# Board.net
KiCad netlist of a schematic drawn in EAGLE
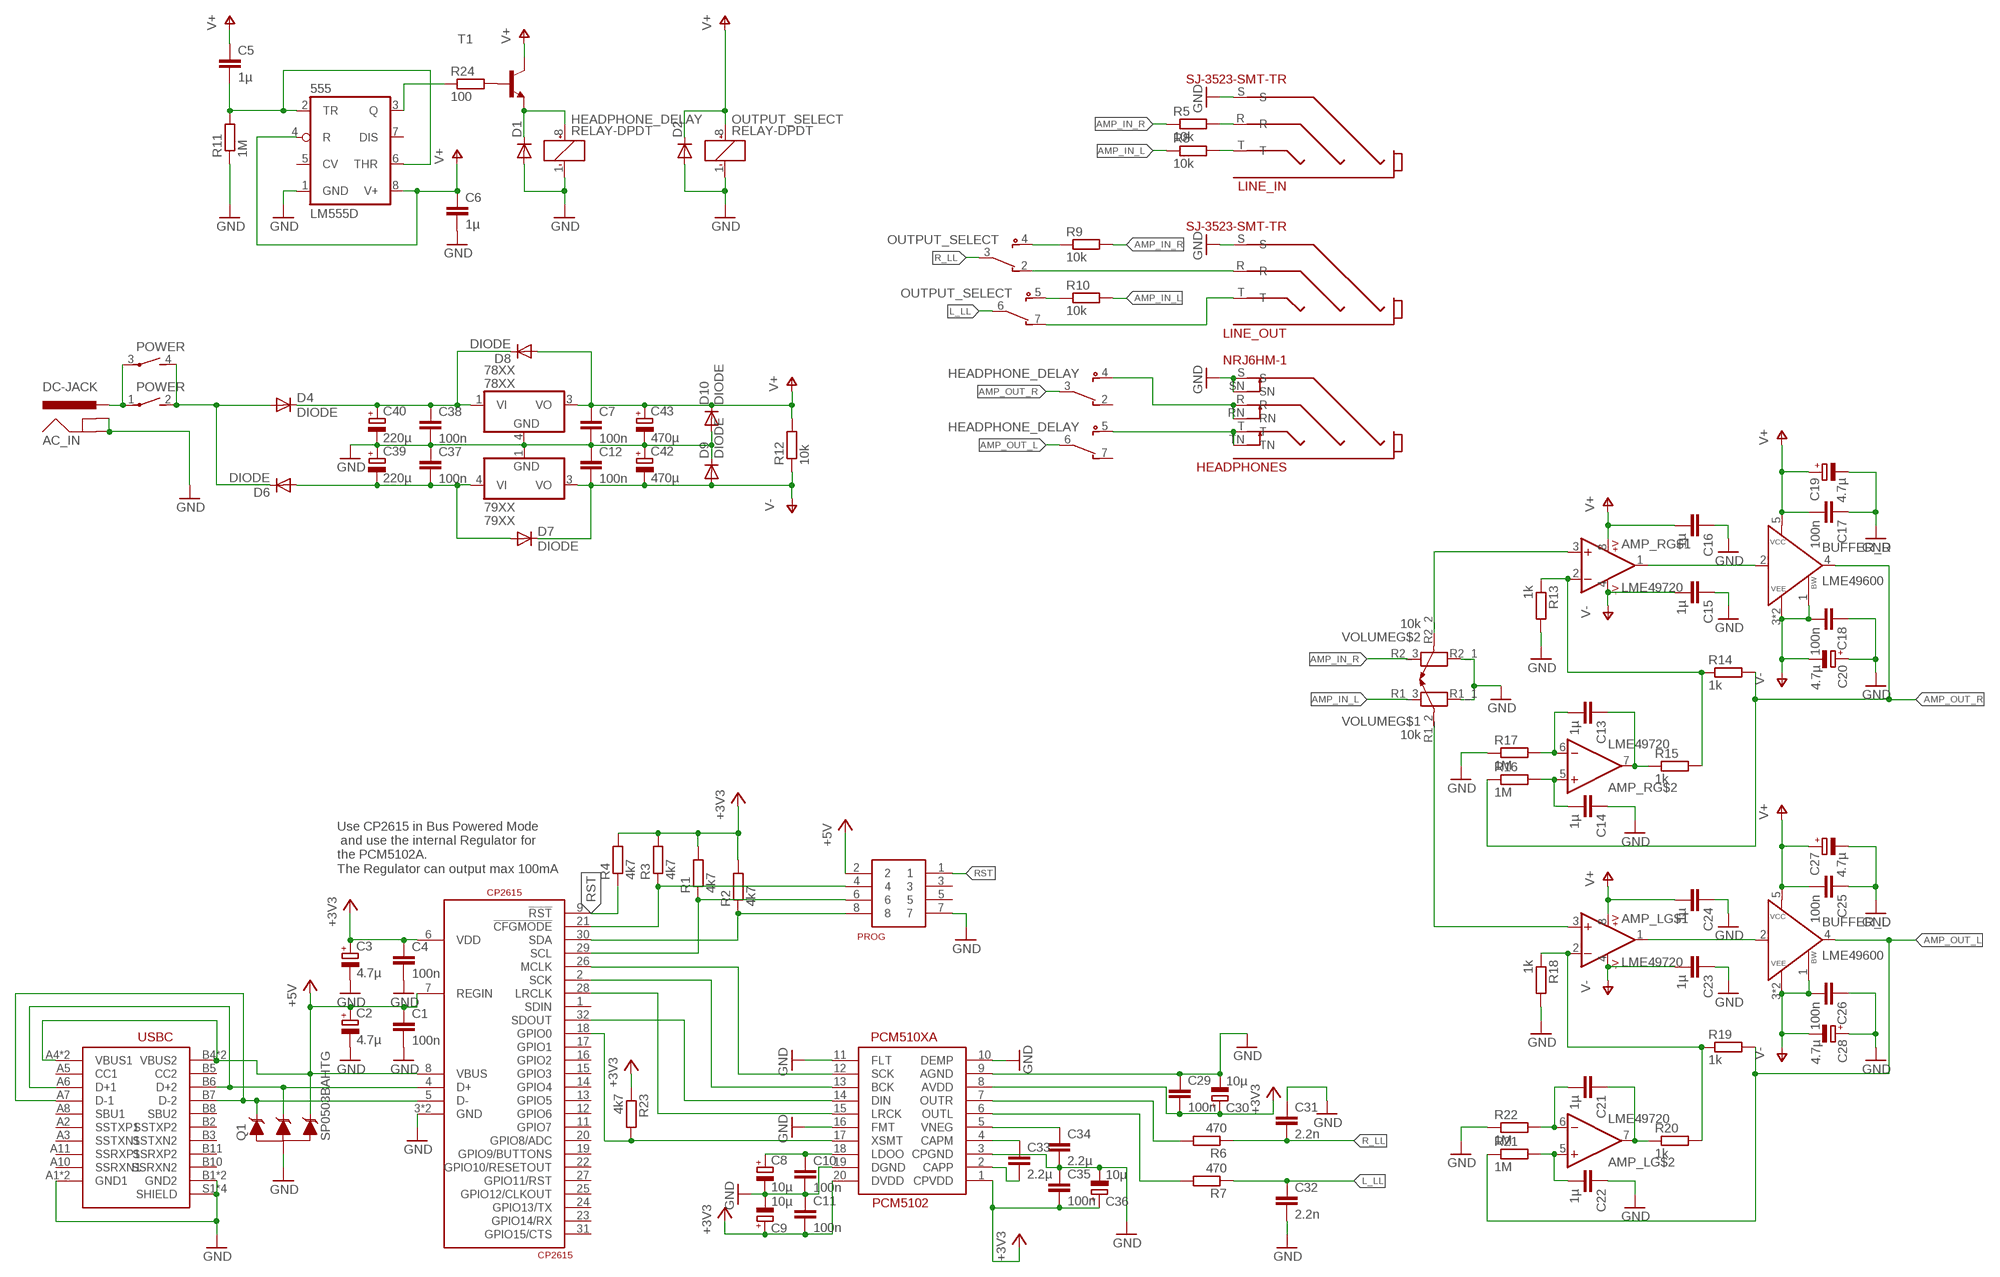
[diagram p0: schematic, sheet 1]

(export (version "E")
  (design (tool "Eeschema 10.0.6"))
  (components
    (comp (ref "78XX")
      (value "78XX")
      (footprint "eagle-import:D2PAK")
      (libsource (lib "eagle-import") (part "78XX"))
    )
    (comp (ref "79XX")
      (value "79XX")
      (footprint "eagle-import:D2PAK")
      (libsource (lib "eagle-import") (part "79XX"))
    )
    (comp (ref "555")
      (value "LM555D")
      (footprint "eagle-import:SO08")
      (libsource (lib "eagle-import") (part "555DLM"))
    )
    (comp (ref "AC_IN")
      (value "DC-JACK")
      (footprint "eagle-import:POWER_JACK_PTH")
      (libsource (lib "eagle-import") (part "DC-JACK"))
    )
    (comp (ref "AMP_L")
      (value "LME49720")
      (footprint "eagle-import:SOIC127P600X175-8")
      (libsource (lib "eagle-import") (part "LME49720"))
    )
    (comp (ref "AMP_R")
      (value "LME49720")
      (footprint "eagle-import:SOIC127P600X175-8")
      (libsource (lib "eagle-import") (part "LME49720"))
    )
    (comp (ref "BUFFER_L")
      (value "LME49600")
      (footprint "eagle-import:TO170P1238X470-6")
      (libsource (lib "eagle-import") (part "LME49600"))
    )
    (comp (ref "BUFFER_R")
      (value "LME49600")
      (footprint "eagle-import:TO170P1238X470-6")
      (libsource (lib "eagle-import") (part "LME49600"))
    )
    (comp (ref "C1")
      (value "100n")
      (footprint "eagle-import:C0603")
      (libsource (lib "eagle-import") (part "C-EUC0603"))
    )
    (comp (ref "C2")
      (value "4.7µ")
      (footprint "eagle-import:UD-4X5,8_NICHICON")
      (libsource (lib "eagle-import") (part "CPOL-EUUD-4X5,8"))
    )
    (comp (ref "C3")
      (value "4.7µ")
      (footprint "eagle-import:UD-4X5,8_NICHICON")
      (libsource (lib "eagle-import") (part "CPOL-EUUD-4X5,8"))
    )
    (comp (ref "C4")
      (value "100n")
      (footprint "eagle-import:C0603")
      (libsource (lib "eagle-import") (part "C-EUC0603"))
    )
    (comp (ref "C5")
      (value "1µ")
      (footprint "eagle-import:C0603")
      (libsource (lib "eagle-import") (part "C-EUC0603"))
    )
    (comp (ref "C6")
      (value "1µ")
      (footprint "eagle-import:C0603")
      (libsource (lib "eagle-import") (part "C-EUC0603"))
    )
    (comp (ref "C7")
      (value "100n")
      (footprint "eagle-import:C0603")
      (libsource (lib "eagle-import") (part "C-EUC0603"))
    )
    (comp (ref "C8")
      (value "10µ")
      (footprint "eagle-import:UD-4X5,8_NICHICON")
      (libsource (lib "eagle-import") (part "CPOL-EUUD-4X5,8"))
    )
    (comp (ref "C9")
      (value "10µ")
      (footprint "eagle-import:UD-4X5,8_NICHICON")
      (libsource (lib "eagle-import") (part "CPOL-EUUD-4X5,8"))
    )
    (comp (ref "C10")
      (value "100n")
      (footprint "eagle-import:C0603")
      (libsource (lib "eagle-import") (part "C-EUC0603"))
    )
    (comp (ref "C11")
      (value "100n")
      (footprint "eagle-import:C0603")
      (libsource (lib "eagle-import") (part "C-EUC0603"))
    )
    (comp (ref "C12")
      (value "100n")
      (footprint "eagle-import:C0603")
      (libsource (lib "eagle-import") (part "C-EUC0603"))
    )
    (comp (ref "C13")
      (value "1µ")
      (footprint "eagle-import:C0603")
      (libsource (lib "eagle-import") (part "C-EUC0603"))
    )
    (comp (ref "C14")
      (value "1µ")
      (footprint "eagle-import:C0603")
      (libsource (lib "eagle-import") (part "C-EUC0603"))
    )
    (comp (ref "C15")
      (value "1µ")
      (footprint "eagle-import:C0603")
      (libsource (lib "eagle-import") (part "C-EUC0603"))
    )
    (comp (ref "C16")
      (value "1µ")
      (footprint "eagle-import:C0603")
      (libsource (lib "eagle-import") (part "C-EUC0603"))
    )
    (comp (ref "C17")
      (value "100n")
      (footprint "eagle-import:C0603")
      (libsource (lib "eagle-import") (part "C-EUC0603"))
    )
    (comp (ref "C18")
      (value "100n")
      (footprint "eagle-import:C0603")
      (libsource (lib "eagle-import") (part "C-EUC0603"))
    )
    (comp (ref "C19")
      (value "4.7µ")
      (footprint "eagle-import:SMC_A")
      (libsource (lib "eagle-import") (part "CPOL-EUSMCA"))
    )
    (comp (ref "C20")
      (value "4.7µ")
      (footprint "eagle-import:SMC_A")
      (libsource (lib "eagle-import") (part "CPOL-EUSMCA"))
    )
    (comp (ref "C21")
      (value "1µ")
      (footprint "eagle-import:C0603")
      (libsource (lib "eagle-import") (part "C-EUC0603"))
    )
    (comp (ref "C22")
      (value "1µ")
      (footprint "eagle-import:C0603")
      (libsource (lib "eagle-import") (part "C-EUC0603"))
    )
    (comp (ref "C23")
      (value "1µ")
      (footprint "eagle-import:C0603")
      (libsource (lib "eagle-import") (part "C-EUC0603"))
    )
    (comp (ref "C24")
      (value "1µ")
      (footprint "eagle-import:C0603")
      (libsource (lib "eagle-import") (part "C-EUC0603"))
    )
    (comp (ref "C25")
      (value "100n")
      (footprint "eagle-import:C0603")
      (libsource (lib "eagle-import") (part "C-EUC0603"))
    )
    (comp (ref "C26")
      (value "100n")
      (footprint "eagle-import:C0603")
      (libsource (lib "eagle-import") (part "C-EUC0603"))
    )
    (comp (ref "C27")
      (value "4.7µ")
      (footprint "eagle-import:SMC_A")
      (libsource (lib "eagle-import") (part "CPOL-EUSMCA"))
    )
    (comp (ref "C28")
      (value "4.7µ")
      (footprint "eagle-import:SMC_A")
      (libsource (lib "eagle-import") (part "CPOL-EUSMCA"))
    )
    (comp (ref "C29")
      (value "100n")
      (footprint "eagle-import:C0603")
      (libsource (lib "eagle-import") (part "C-EUC0603"))
    )
    (comp (ref "C30")
      (value "10µ")
      (footprint "eagle-import:UD-4X5,8_NICHICON")
      (libsource (lib "eagle-import") (part "CPOL-EUUD-4X5,8"))
    )
    (comp (ref "C31")
      (value "2.2n")
      (footprint "eagle-import:C0603")
      (libsource (lib "eagle-import") (part "C-EUC0603"))
    )
    (comp (ref "C32")
      (value "2.2n")
      (footprint "eagle-import:C0603")
      (libsource (lib "eagle-import") (part "C-EUC0603"))
    )
    (comp (ref "C33")
      (value "2.2µ")
      (footprint "eagle-import:C0603")
      (libsource (lib "eagle-import") (part "C-EUC0603"))
    )
    (comp (ref "C34")
      (value "2.2µ")
      (footprint "eagle-import:C0603")
      (libsource (lib "eagle-import") (part "C-EUC0603"))
    )
    (comp (ref "C35")
      (value "100n")
      (footprint "eagle-import:C0603")
      (libsource (lib "eagle-import") (part "C-EUC0603"))
    )
    (comp (ref "C36")
      (value "10µ")
      (footprint "eagle-import:UD-4X5,8_NICHICON")
      (libsource (lib "eagle-import") (part "CPOL-EUUD-4X5,8"))
    )
    (comp (ref "C37")
      (value "100n")
      (footprint "eagle-import:C0603")
      (libsource (lib "eagle-import") (part "C-EUC0603"))
    )
    (comp (ref "C38")
      (value "100n")
      (footprint "eagle-import:C0603")
      (libsource (lib "eagle-import") (part "C-EUC0603"))
    )
    (comp (ref "C39")
      (value "220µ")
      (footprint "eagle-import:175TMP-0810")
      (libsource (lib "eagle-import") (part "CPOL-EU175TMP-0810"))
    )
    (comp (ref "C40")
      (value "220µ")
      (footprint "eagle-import:175TMP-0810")
      (libsource (lib "eagle-import") (part "CPOL-EU175TMP-0810"))
    )
    (comp (ref "C42")
      (value "470µ")
      (footprint "eagle-import:175TMP-0810")
      (libsource (lib "eagle-import") (part "CPOL-EU175TMP-0810"))
    )
    (comp (ref "C43")
      (value "470µ")
      (footprint "eagle-import:175TMP-0810")
      (libsource (lib "eagle-import") (part "CPOL-EU175TMP-0810"))
    )
    (comp (ref "CP2615")
      (value "CP2615")
      (footprint "eagle-import:QFN50P500X500X90-32")
      (libsource (lib "eagle-import") (part "CP2615"))
    )
    (comp (ref "D1")
      (value "DIODE-SOD323-W")
      (footprint "eagle-import:SOD323-W")
      (libsource (lib "eagle-import") (part "DIODE-SOD323-W"))
    )
    (comp (ref "D2")
      (value "DIODE-SOD323-W")
      (footprint "eagle-import:SOD323-W")
      (libsource (lib "eagle-import") (part "DIODE-SOD323-W"))
    )
    (comp (ref "D4")
      (value "DIODE")
      (footprint "eagle-import:SODFL5024X231")
      (libsource (lib "eagle-import") (part "DIODE"))
    )
    (comp (ref "D6")
      (value "DIODE")
      (footprint "eagle-import:SODFL5024X231")
      (libsource (lib "eagle-import") (part "DIODE"))
    )
    (comp (ref "D7")
      (value "DIODE")
      (footprint "eagle-import:SODFL5024X231")
      (libsource (lib "eagle-import") (part "DIODE"))
    )
    (comp (ref "D8")
      (value "DIODE")
      (footprint "eagle-import:SODFL5024X231")
      (libsource (lib "eagle-import") (part "DIODE"))
    )
    (comp (ref "D9")
      (value "DIODE")
      (footprint "eagle-import:SODFL5024X231")
      (libsource (lib "eagle-import") (part "DIODE"))
    )
    (comp (ref "D10")
      (value "DIODE")
      (footprint "eagle-import:SODFL5024X231")
      (libsource (lib "eagle-import") (part "DIODE"))
    )
    (comp (ref "HEADPHONES")
      (value "NRJ6HM-1")
      (footprint "eagle-import:NRJ6HM-1")
      (libsource (lib "eagle-import") (part "NRJ6HM-1"))
    )
    (comp (ref "HEADPHONE_DELAY")
      (value "RELAY-DPDT")
      (footprint "eagle-import:KEMET-UD2")
      (libsource (lib "eagle-import") (part "RELAY-DPDT"))
    )
    (comp (ref "LINE_IN")
      (value "SJ-3523-SMT-TR")
      (footprint "eagle-import:SJ-352X-SMT-TR")
      (libsource (lib "eagle-import") (part "SJ-3523-SMT-TR"))
    )
    (comp (ref "LINE_OUT")
      (value "SJ-3523-SMT-TR")
      (footprint "eagle-import:SJ-352X-SMT-TR")
      (libsource (lib "eagle-import") (part "SJ-3523-SMT-TR"))
    )
    (comp (ref "OUTPUT_SELECT")
      (value "RELAY-DPDT")
      (footprint "eagle-import:KEMET-UD2")
      (libsource (lib "eagle-import") (part "RELAY-DPDT"))
    )
    (comp (ref "PCM5102")
      (value "PCM510XA")
      (footprint "eagle-import:SOP65P640X120-20")
      (libsource (lib "eagle-import") (part "PCM510XA"))
    )
    (comp (ref "POWER")
      (value "PB400")
      (footprint "eagle-import:PB400")
      (libsource (lib "eagle-import") (part "PB400"))
    )
    (comp (ref "PROG")
      (value "2X4_HEADER")
      (footprint "eagle-import:2X4_0.5_HEADER_SMD")
      (libsource (lib "eagle-import") (part "2X4_HEADER"))
    )
    (comp (ref "Q1")
      (value "SP0503BAHTG")
      (footprint "eagle-import:SOT192P237X122-4")
      (libsource (lib "eagle-import") (part "SP0503BAHTG"))
    )
    (comp (ref "R1")
      (value "4k7")
      (footprint "eagle-import:R0603")
      (libsource (lib "eagle-import") (part "R-EU_R0603"))
    )
    (comp (ref "R2")
      (value "4k7")
      (footprint "eagle-import:R0603")
      (libsource (lib "eagle-import") (part "R-EU_R0603"))
    )
    (comp (ref "R3")
      (value "4k7")
      (footprint "eagle-import:R0603")
      (libsource (lib "eagle-import") (part "R-EU_R0603"))
    )
    (comp (ref "R4")
      (value "4k7")
      (footprint "eagle-import:R0603")
      (libsource (lib "eagle-import") (part "R-EU_R0603"))
    )
    (comp (ref "R5")
      (value "10k")
      (footprint "eagle-import:R0603")
      (libsource (lib "eagle-import") (part "R-EU_R0603"))
    )
    (comp (ref "R6")
      (value "470")
      (footprint "eagle-import:R0603")
      (libsource (lib "eagle-import") (part "R-EU_R0603"))
    )
    (comp (ref "R7")
      (value "470")
      (footprint "eagle-import:R0603")
      (libsource (lib "eagle-import") (part "R-EU_R0603"))
    )
    (comp (ref "R8")
      (value "10k")
      (footprint "eagle-import:R0603")
      (libsource (lib "eagle-import") (part "R-EU_R0603"))
    )
    (comp (ref "R9")
      (value "10k")
      (footprint "eagle-import:R0603")
      (libsource (lib "eagle-import") (part "R-EU_R0603"))
    )
    (comp (ref "R10")
      (value "10k")
      (footprint "eagle-import:R0603")
      (libsource (lib "eagle-import") (part "R-EU_R0603"))
    )
    (comp (ref "R11")
      (value "1M")
      (footprint "eagle-import:R0603")
      (libsource (lib "eagle-import") (part "R-EU_R0603"))
    )
    (comp (ref "R12")
      (value "10k")
      (footprint "eagle-import:R0603")
      (libsource (lib "eagle-import") (part "R-EU_R0603"))
    )
    (comp (ref "R13")
      (value "1k")
      (footprint "eagle-import:R0603")
      (libsource (lib "eagle-import") (part "R-EU_R0603"))
    )
    (comp (ref "R14")
      (value "1k")
      (footprint "eagle-import:R0603")
      (libsource (lib "eagle-import") (part "R-EU_R0603"))
    )
    (comp (ref "R15")
      (value "1k")
      (footprint "eagle-import:R0603")
      (libsource (lib "eagle-import") (part "R-EU_R0603"))
    )
    (comp (ref "R16")
      (value "1M")
      (footprint "eagle-import:R0603")
      (libsource (lib "eagle-import") (part "R-EU_R0603"))
    )
    (comp (ref "R17")
      (value "1M")
      (footprint "eagle-import:R0603")
      (libsource (lib "eagle-import") (part "R-EU_R0603"))
    )
    (comp (ref "R18")
      (value "1k")
      (footprint "eagle-import:R0603")
      (libsource (lib "eagle-import") (part "R-EU_R0603"))
    )
    (comp (ref "R19")
      (value "1k")
      (footprint "eagle-import:R0603")
      (libsource (lib "eagle-import") (part "R-EU_R0603"))
    )
    (comp (ref "R20")
      (value "1k")
      (footprint "eagle-import:R0603")
      (libsource (lib "eagle-import") (part "R-EU_R0603"))
    )
    (comp (ref "R21")
      (value "1M")
      (footprint "eagle-import:R0603")
      (libsource (lib "eagle-import") (part "R-EU_R0603"))
    )
    (comp (ref "R22")
      (value "1M")
      (footprint "eagle-import:R0603")
      (libsource (lib "eagle-import") (part "R-EU_R0603"))
    )
    (comp (ref "R23")
      (value "4k7")
      (footprint "eagle-import:R0603")
      (libsource (lib "eagle-import") (part "R-EU_R0603"))
    )
    (comp (ref "R24")
      (value "100")
      (footprint "eagle-import:R0603")
      (libsource (lib "eagle-import") (part "R-EU_R0603"))
    )
    (comp (ref "T1")
      (value "BC817-16-NPN-SOT23-BEC")
      (footprint "eagle-import:SOT23-BEC")
      (libsource (lib "eagle-import") (part "-NPN-SOT23-BECBC817-16"))
    )
    (comp (ref "U$2")
      (value "UJ31-CH-3-SMT-TR")
      (footprint "eagle-import:UJ31-CH-3-SMT-TR")
      (libsource (lib "eagle-import") (part "UJ31-CH-3-SMT-TR"))
    )
    (comp (ref "VOLUME")
      (value "10k")
      (footprint "eagle-import:ALPS-RK09L12B0")
      (libsource (lib "eagle-import") (part "ALPS-RK09L12B0"))
    )
  )
  (nets
    (net (code "1") (name "+3V3") (class "Default")
      (node (ref "C11") (pin "2") (pinfunction "2_2") (pintype "passive"))
      (node (ref "C29") (pin "2") (pinfunction "2_2") (pintype "passive"))
      (node (ref "C3") (pin "+") (pinfunction "+_+") (pintype "passive"))
      (node (ref "C30") (pin "+") (pinfunction "+_+") (pintype "passive"))
      (node (ref "C35") (pin "2") (pinfunction "2_2") (pintype "passive"))
      (node (ref "C36") (pin "+") (pinfunction "+_+") (pintype "passive"))
      (node (ref "C4") (pin "1") (pinfunction "1_1") (pintype "passive"))
      (node (ref "C9") (pin "+") (pinfunction "+_+") (pintype "passive"))
      (node (ref "CP2615") (pin "6") (pinfunction "VDD_6") (pintype "bidirectional"))
      (node (ref "PCM5102") (pin "1") (pinfunction "CPVDD_1") (pintype "bidirectional"))
      (node (ref "PCM5102") (pin "20") (pinfunction "DVDD_20") (pintype "bidirectional"))
      (node (ref "PCM5102") (pin "8") (pinfunction "AVDD_8") (pintype "bidirectional"))
      (node (ref "R1") (pin "2") (pinfunction "2_2") (pintype "passive"))
      (node (ref "R2") (pin "2") (pinfunction "2_2") (pintype "passive"))
      (node (ref "R23") (pin "1") (pinfunction "1_1") (pintype "passive"))
      (node (ref "R3") (pin "2") (pinfunction "2_2") (pintype "passive"))
      (node (ref "R4") (pin "2") (pinfunction "2_2") (pintype "passive"))
    )
    (net (code "2") (name "+5V") (class "Default")
      (node (ref "C1") (pin "1") (pinfunction "1_1") (pintype "passive"))
      (node (ref "C2") (pin "+") (pinfunction "+_+") (pintype "passive"))
      (node (ref "CP2615") (pin "7") (pinfunction "REGIN_7") (pintype "bidirectional"))
      (node (ref "CP2615") (pin "8") (pinfunction "VBUS_8") (pintype "bidirectional"))
      (node (ref "PROG") (pin "2") (pinfunction "2_2") (pintype "bidirectional"))
      (node (ref "Q1") (pin "4") (pinfunction "C3_4") (pintype "passive"))
      (node (ref "U$2") (pin "A4") (pinfunction "VBUS1_A4") (pintype "power_in"))
      (node (ref "U$2") (pin "A9") (pinfunction "VBUS1_A9") (pintype "power_in"))
      (node (ref "U$2") (pin "B4") (pinfunction "VBUS2_B4") (pintype "power_in"))
      (node (ref "U$2") (pin "B9") (pinfunction "VBUS2_B9") (pintype "power_in"))
    )
    (net (code "3") (name "AMP_IN_L") (class "Default")
      (node (ref "R10") (pin "2") (pinfunction "2_2") (pintype "passive"))
      (node (ref "R8") (pin "1") (pinfunction "1_1") (pintype "passive"))
      (node (ref "VOLUME") (pin "R1_3") (pinfunction "2_R1_3") (pintype "passive"))
    )
    (net (code "4") (name "AMP_IN_R") (class "Default")
      (node (ref "R5") (pin "1") (pinfunction "1_1") (pintype "passive"))
      (node (ref "R9") (pin "2") (pinfunction "2_2") (pintype "passive"))
      (node (ref "VOLUME") (pin "R2_3") (pinfunction "2_R2_3") (pintype "passive"))
    )
    (net (code "5") (name "AMP_OUT_L") (class "Default")
      (node (ref "BUFFER_L") (pin "4") (pinfunction "OUT_4") (pintype "output"))
      (node (ref "HEADPHONE_DELAY") (pin "6") (pinfunction "W_6") (pintype "passive"))
      (node (ref "R19") (pin "2") (pinfunction "2_2") (pintype "passive"))
      (node (ref "R21") (pin "1") (pinfunction "1_1") (pintype "passive"))
    )
    (net (code "6") (name "AMP_OUT_R") (class "Default")
      (node (ref "BUFFER_R") (pin "4") (pinfunction "OUT_4") (pintype "output"))
      (node (ref "HEADPHONE_DELAY") (pin "3") (pinfunction "W_3") (pintype "passive"))
      (node (ref "R14") (pin "2") (pinfunction "2_2") (pintype "passive"))
      (node (ref "R16") (pin "1") (pinfunction "1_1") (pintype "passive"))
    )
    (net (code "7") (name "GND") (class "Default")
      (node (ref "555") (pin "1") (pinfunction "GND_1") (pintype "power_in"))
      (node (ref "78XX") (pin "4") (pinfunction "GND_4") (pintype "passive"))
      (node (ref "79XX") (pin "1") (pinfunction "GND_1") (pintype "passive"))
      (node (ref "AC_IN") (pin "GND") (pinfunction "GND_GND") (pintype "bidirectional"))
      (node (ref "AC_IN") (pin "GNDBREAK") (pinfunction "GNDBREAK_GNDBREAK") (pintype "bidirectional"))
      (node (ref "C1") (pin "2") (pinfunction "2_2") (pintype "passive"))
      (node (ref "C10") (pin "2") (pinfunction "2_2") (pintype "passive"))
      (node (ref "C11") (pin "1") (pinfunction "1_1") (pintype "passive"))
      (node (ref "C12") (pin "1") (pinfunction "1_1") (pintype "passive"))
      (node (ref "C14") (pin "1") (pinfunction "1_1") (pintype "passive"))
      (node (ref "C15") (pin "1") (pinfunction "1_1") (pintype "passive"))
      (node (ref "C16") (pin "1") (pinfunction "1_1") (pintype "passive"))
      (node (ref "C17") (pin "1") (pinfunction "1_1") (pintype "passive"))
      (node (ref "C18") (pin "1") (pinfunction "1_1") (pintype "passive"))
      (node (ref "C19") (pin "-") (pinfunction "-_-") (pintype "passive"))
      (node (ref "C2") (pin "-") (pinfunction "-_-") (pintype "passive"))
      (node (ref "C20") (pin "+") (pinfunction "+_+") (pintype "passive"))
      (node (ref "C22") (pin "1") (pinfunction "1_1") (pintype "passive"))
      (node (ref "C23") (pin "1") (pinfunction "1_1") (pintype "passive"))
      (node (ref "C24") (pin "1") (pinfunction "1_1") (pintype "passive"))
      (node (ref "C25") (pin "1") (pinfunction "1_1") (pintype "passive"))
      (node (ref "C26") (pin "1") (pinfunction "1_1") (pintype "passive"))
      (node (ref "C27") (pin "-") (pinfunction "-_-") (pintype "passive"))
      (node (ref "C28") (pin "+") (pinfunction "+_+") (pintype "passive"))
      (node (ref "C29") (pin "1") (pinfunction "1_1") (pintype "passive"))
      (node (ref "C3") (pin "-") (pinfunction "-_-") (pintype "passive"))
      (node (ref "C30") (pin "-") (pinfunction "-_-") (pintype "passive"))
      (node (ref "C31") (pin "1") (pinfunction "1_1") (pintype "passive"))
      (node (ref "C32") (pin "2") (pinfunction "2_2") (pintype "passive"))
      (node (ref "C34") (pin "2") (pinfunction "2_2") (pintype "passive"))
      (node (ref "C35") (pin "1") (pinfunction "1_1") (pintype "passive"))
      (node (ref "C36") (pin "-") (pinfunction "-_-") (pintype "passive"))
      (node (ref "C37") (pin "1") (pinfunction "1_1") (pintype "passive"))
      (node (ref "C38") (pin "2") (pinfunction "2_2") (pintype "passive"))
      (node (ref "C39") (pin "+") (pinfunction "+_+") (pintype "passive"))
      (node (ref "C4") (pin "2") (pinfunction "2_2") (pintype "passive"))
      (node (ref "C40") (pin "-") (pinfunction "-_-") (pintype "passive"))
      (node (ref "C42") (pin "+") (pinfunction "+_+") (pintype "passive"))
      (node (ref "C43") (pin "-") (pinfunction "-_-") (pintype "passive"))
      (node (ref "C6") (pin "2") (pinfunction "2_2") (pintype "passive"))
      (node (ref "C7") (pin "2") (pinfunction "2_2") (pintype "passive"))
      (node (ref "C8") (pin "-") (pinfunction "-_-") (pintype "passive"))
      (node (ref "C9") (pin "-") (pinfunction "-_-") (pintype "passive"))
      (node (ref "CP2615") (pin "3") (pinfunction "GND_3") (pintype "bidirectional"))
      (node (ref "CP2615") (pin "PAD") (pinfunction "GND_PAD") (pintype "bidirectional"))
      (node (ref "D1") (pin "A") (pinfunction "A_A") (pintype "passive"))
      (node (ref "D10") (pin "A") (pinfunction "A_A") (pintype "passive"))
      (node (ref "D2") (pin "A") (pinfunction "A_A") (pintype "passive"))
      (node (ref "D9") (pin "C") (pinfunction "C_C") (pintype "passive"))
      (node (ref "HEADPHONES") (pin "S") (pinfunction "S_S") (pintype "bidirectional"))
      (node (ref "HEADPHONES") (pin "SN") (pinfunction "SN_SN") (pintype "bidirectional"))
      (node (ref "HEADPHONE_DELAY") (pin "1") (pinfunction "-_1") (pintype "passive"))
      (node (ref "LINE_IN") (pin "S") (pinfunction "S_S") (pintype "bidirectional"))
      (node (ref "LINE_OUT") (pin "S") (pinfunction "S_S") (pintype "bidirectional"))
      (node (ref "OUTPUT_SELECT") (pin "1") (pinfunction "-_1") (pintype "passive"))
      (node (ref "PCM5102") (pin "10") (pinfunction "DEMP_10") (pintype "bidirectional"))
      (node (ref "PCM5102") (pin "11") (pinfunction "FLT_11") (pintype "bidirectional"))
      (node (ref "PCM5102") (pin "16") (pinfunction "FMT_16") (pintype "bidirectional"))
      (node (ref "PCM5102") (pin "19") (pinfunction "DGND_19") (pintype "bidirectional"))
      (node (ref "PCM5102") (pin "3") (pinfunction "CPGND_3") (pintype "bidirectional"))
      (node (ref "PCM5102") (pin "9") (pinfunction "AGND_9") (pintype "bidirectional"))
      (node (ref "PROG") (pin "7") (pinfunction "7_7") (pintype "bidirectional"))
      (node (ref "Q1") (pin "1") (pinfunction "A_1") (pintype "passive"))
      (node (ref "R11") (pin "1") (pinfunction "1_1") (pintype "passive"))
      (node (ref "R13") (pin "2") (pinfunction "2_2") (pintype "passive"))
      (node (ref "R17") (pin "1") (pinfunction "1_1") (pintype "passive"))
      (node (ref "R18") (pin "2") (pinfunction "2_2") (pintype "passive"))
      (node (ref "R22") (pin "1") (pinfunction "1_1") (pintype "passive"))
      (node (ref "U$2") (pin "A1") (pinfunction "GND1_A1") (pintype "power_in"))
      (node (ref "U$2") (pin "A12") (pinfunction "GND1_A12") (pintype "power_in"))
      (node (ref "U$2") (pin "B1") (pinfunction "GND2_B1") (pintype "power_in"))
      (node (ref "U$2") (pin "B12") (pinfunction "GND2_B12") (pintype "power_in"))
      (node (ref "U$2") (pin "S1") (pinfunction "SHIELD_S1") (pintype "bidirectional"))
      (node (ref "U$2") (pin "S2") (pinfunction "SHIELD_S2") (pintype "bidirectional"))
      (node (ref "U$2") (pin "S3") (pinfunction "SHIELD_S3") (pintype "bidirectional"))
      (node (ref "U$2") (pin "S4") (pinfunction "SHIELD_S4") (pintype "bidirectional"))
      (node (ref "VOLUME") (pin "R1_1") (pinfunction "1_R1_1") (pintype "passive"))
      (node (ref "VOLUME") (pin "R2_1") (pinfunction "1_R2_1") (pintype "passive"))
    )
    (net (code "8") (name "L_LL") (class "Default")
      (node (ref "C32") (pin "1") (pinfunction "1_1") (pintype "passive"))
      (node (ref "OUTPUT_SELECT") (pin "6") (pinfunction "W_6") (pintype "passive"))
      (node (ref "R7") (pin "1") (pinfunction "1_1") (pintype "passive"))
    )
    (net (code "9") (name "Net-(78XX-VI)") (class "Default")
      (node (ref "78XX") (pin "1") (pinfunction "VI_1") (pintype "input"))
      (node (ref "C38") (pin "1") (pinfunction "1_1") (pintype "passive"))
      (node (ref "C40") (pin "+") (pinfunction "+_+") (pintype "passive"))
      (node (ref "D4") (pin "C") (pinfunction "C_C") (pintype "passive"))
      (node (ref "D8") (pin "C") (pinfunction "C_C") (pintype "passive"))
    )
    (net (code "10") (name "Net-(79XX-VI)") (class "Default")
      (node (ref "79XX") (pin "4") (pinfunction "VI_4") (pintype "input"))
      (node (ref "C37") (pin "2") (pinfunction "2_2") (pintype "passive"))
      (node (ref "C39") (pin "-") (pinfunction "-_-") (pintype "passive"))
      (node (ref "D6") (pin "A") (pinfunction "A_A") (pintype "passive"))
      (node (ref "D7") (pin "A") (pinfunction "A_A") (pintype "passive"))
    )
    (net (code "11") (name "Net-(555-Q)") (class "Default")
      (node (ref "555") (pin "3") (pinfunction "Q_3") (pintype "output"))
      (node (ref "R24") (pin "1") (pinfunction "1_1") (pintype "passive"))
    )
    (net (code "12") (name "Net-(555-THR)") (class "Default")
      (node (ref "555") (pin "2") (pinfunction "TR_2") (pintype "input"))
      (node (ref "555") (pin "6") (pinfunction "THR_6") (pintype "input"))
      (node (ref "C5") (pin "2") (pinfunction "2_2") (pintype "passive"))
      (node (ref "R11") (pin "2") (pinfunction "2_2") (pintype "passive"))
    )
    (net (code "13") (name "Net-(AMP_LA-+IN)") (class "Default")
      (node (ref "AMP_L") (pin "3") (pinfunction "+IN_3") (pintype "input"))
      (node (ref "VOLUME") (pin "R1_2") (pinfunction "3_R1_2") (pintype "passive"))
    )
    (net (code "14") (name "Net-(AMP_LA--IN)") (class "Default")
      (node (ref "AMP_L") (pin "2") (pinfunction "-IN_2") (pintype "input"))
      (node (ref "R18") (pin "1") (pinfunction "1_1") (pintype "passive"))
      (node (ref "R19") (pin "1") (pinfunction "1_1") (pintype "passive"))
      (node (ref "R20") (pin "2") (pinfunction "2_2") (pintype "passive"))
    )
    (net (code "15") (name "Net-(AMP_LA-OUT)") (class "Default")
      (node (ref "AMP_L") (pin "1") (pinfunction "OUT_1") (pintype "output"))
      (node (ref "BUFFER_L") (pin "2") (pinfunction "IN_2") (pintype "input"))
    )
    (net (code "16") (name "Net-(AMP_LB-+IN)") (class "Default")
      (node (ref "AMP_L") (pin "5") (pinfunction "+IN_5") (pintype "input"))
      (node (ref "C22") (pin "2") (pinfunction "2_2") (pintype "passive"))
      (node (ref "R21") (pin "2") (pinfunction "2_2") (pintype "passive"))
    )
    (net (code "17") (name "Net-(AMP_LB--IN)") (class "Default")
      (node (ref "AMP_L") (pin "6") (pinfunction "-IN_6") (pintype "input"))
      (node (ref "C21") (pin "2") (pinfunction "2_2") (pintype "passive"))
      (node (ref "R22") (pin "2") (pinfunction "2_2") (pintype "passive"))
    )
    (net (code "18") (name "Net-(AMP_LB-OUT)") (class "Default")
      (node (ref "AMP_L") (pin "7") (pinfunction "OUT_7") (pintype "output"))
      (node (ref "C21") (pin "1") (pinfunction "1_1") (pintype "passive"))
      (node (ref "R20") (pin "1") (pinfunction "1_1") (pintype "passive"))
    )
    (net (code "19") (name "Net-(AMP_RA-+IN)") (class "Default")
      (node (ref "AMP_R") (pin "3") (pinfunction "+IN_3") (pintype "input"))
      (node (ref "VOLUME") (pin "R2_2") (pinfunction "3_R2_2") (pintype "passive"))
    )
    (net (code "20") (name "Net-(AMP_RA--IN)") (class "Default")
      (node (ref "AMP_R") (pin "2") (pinfunction "-IN_2") (pintype "input"))
      (node (ref "R13") (pin "1") (pinfunction "1_1") (pintype "passive"))
      (node (ref "R14") (pin "1") (pinfunction "1_1") (pintype "passive"))
      (node (ref "R15") (pin "2") (pinfunction "2_2") (pintype "passive"))
    )
    (net (code "21") (name "Net-(AMP_RA-OUT)") (class "Default")
      (node (ref "AMP_R") (pin "1") (pinfunction "OUT_1") (pintype "output"))
      (node (ref "BUFFER_R") (pin "2") (pinfunction "IN_2") (pintype "input"))
    )
    (net (code "22") (name "Net-(AMP_RB-+IN)") (class "Default")
      (node (ref "AMP_R") (pin "5") (pinfunction "+IN_5") (pintype "input"))
      (node (ref "C14") (pin "2") (pinfunction "2_2") (pintype "passive"))
      (node (ref "R16") (pin "2") (pinfunction "2_2") (pintype "passive"))
    )
    (net (code "23") (name "Net-(AMP_RB--IN)") (class "Default")
      (node (ref "AMP_R") (pin "6") (pinfunction "-IN_6") (pintype "input"))
      (node (ref "C13") (pin "2") (pinfunction "2_2") (pintype "passive"))
      (node (ref "R17") (pin "2") (pinfunction "2_2") (pintype "passive"))
    )
    (net (code "24") (name "Net-(AMP_RB-OUT)") (class "Default")
      (node (ref "AMP_R") (pin "7") (pinfunction "OUT_7") (pintype "output"))
      (node (ref "C13") (pin "1") (pinfunction "1_1") (pintype "passive"))
      (node (ref "R15") (pin "1") (pinfunction "1_1") (pintype "passive"))
    )
    (net (code "25") (name "Net-(CP2615-D+)") (class "Default")
      (node (ref "CP2615") (pin "4") (pinfunction "D+_4") (pintype "bidirectional"))
      (node (ref "Q1") (pin "3") (pinfunction "C2_3") (pintype "passive"))
      (node (ref "U$2") (pin "A6") (pinfunction "D+1_A6") (pintype "bidirectional"))
      (node (ref "U$2") (pin "B6") (pinfunction "D+2_B6") (pintype "bidirectional"))
    )
    (net (code "26") (name "Net-(CP2615-D-)") (class "Default")
      (node (ref "CP2615") (pin "5") (pinfunction "D-_5") (pintype "bidirectional"))
      (node (ref "Q1") (pin "2") (pinfunction "C1_2") (pintype "passive"))
      (node (ref "U$2") (pin "A7") (pinfunction "D-1_A7") (pintype "bidirectional"))
      (node (ref "U$2") (pin "B7") (pinfunction "D-2_B7") (pintype "bidirectional"))
    )
    (net (code "27") (name "Net-(CP2615-GPIO0)") (class "Default")
      (node (ref "CP2615") (pin "18") (pinfunction "GPIO0_18") (pintype "bidirectional"))
      (node (ref "PCM5102") (pin "17") (pinfunction "XSMT_17") (pintype "bidirectional"))
      (node (ref "R23") (pin "2") (pinfunction "2_2") (pintype "passive"))
    )
    (net (code "28") (name "Net-(CP2615-LRCLK)") (class "Default")
      (node (ref "CP2615") (pin "28") (pinfunction "LRCLK_28") (pintype "bidirectional"))
      (node (ref "PCM5102") (pin "15") (pinfunction "LRCK_15") (pintype "bidirectional"))
    )
    (net (code "29") (name "Net-(CP2615-MCLK)") (class "Default")
      (node (ref "CP2615") (pin "26") (pinfunction "MCLK_26") (pintype "bidirectional"))
      (node (ref "PCM5102") (pin "12") (pinfunction "SCK_12") (pintype "bidirectional"))
    )
    (net (code "30") (name "Net-(CP2615-SCK)") (class "Default")
      (node (ref "CP2615") (pin "2") (pinfunction "SCK_2") (pintype "bidirectional"))
      (node (ref "PCM5102") (pin "13") (pinfunction "BCK_13") (pintype "bidirectional"))
    )
    (net (code "31") (name "Net-(CP2615-SCL)") (class "Default")
      (node (ref "CP2615") (pin "29") (pinfunction "SCL_29") (pintype "bidirectional"))
      (node (ref "PROG") (pin "6") (pinfunction "6_6") (pintype "bidirectional"))
      (node (ref "R1") (pin "1") (pinfunction "1_1") (pintype "passive"))
    )
    (net (code "32") (name "Net-(CP2615-SDA)") (class "Default")
      (node (ref "CP2615") (pin "30") (pinfunction "SDA_30") (pintype "bidirectional"))
      (node (ref "PROG") (pin "8") (pinfunction "8_8") (pintype "bidirectional"))
      (node (ref "R2") (pin "1") (pinfunction "1_1") (pintype "passive"))
    )
    (net (code "33") (name "Net-(CP2615-SDOUT)") (class "Default")
      (node (ref "CP2615") (pin "32") (pinfunction "SDOUT_32") (pintype "bidirectional"))
      (node (ref "PCM5102") (pin "14") (pinfunction "DIN_14") (pintype "bidirectional"))
    )
    (net (code "34") (name "Net-(CP2615-~{CFGMODE})") (class "Default")
      (node (ref "CP2615") (pin "21") (pinfunction "~{CFGMODE}_21") (pintype "bidirectional"))
      (node (ref "PROG") (pin "4") (pinfunction "4_4") (pintype "bidirectional"))
      (node (ref "R3") (pin "1") (pinfunction "1_1") (pintype "passive"))
    )
    (net (code "35") (name "Net-(HEADPHONE_DELAYA-+)") (class "Default")
      (node (ref "D1") (pin "C") (pinfunction "C_C") (pintype "passive"))
      (node (ref "HEADPHONE_DELAY") (pin "8") (pinfunction "+_8") (pintype "passive"))
      (node (ref "T1") (pin "E") (pinfunction "E_E") (pintype "passive"))
    )
    (net (code "36") (name "Net-(HEADPHONE_DELAYB-NO)") (class "Default")
      (node (ref "HEADPHONES") (pin "R") (pinfunction "R_R") (pintype "bidirectional"))
      (node (ref "HEADPHONES") (pin "RN") (pinfunction "RN_RN") (pintype "bidirectional"))
      (node (ref "HEADPHONE_DELAY") (pin "4") (pinfunction "NO_4") (pintype "passive"))
    )
    (net (code "37") (name "Net-(HEADPHONE_DELAYC-NO)") (class "Default")
      (node (ref "HEADPHONES") (pin "T") (pinfunction "T_T") (pintype "bidirectional"))
      (node (ref "HEADPHONES") (pin "TN") (pinfunction "TN_TN") (pintype "bidirectional"))
      (node (ref "HEADPHONE_DELAY") (pin "5") (pinfunction "NO_5") (pintype "passive"))
    )
    (net (code "38") (name "Net-(LINE_IN-PadR)") (class "Default")
      (node (ref "LINE_IN") (pin "R") (pinfunction "R_R") (pintype "bidirectional"))
      (node (ref "R5") (pin "2") (pinfunction "2_2") (pintype "passive"))
    )
    (net (code "39") (name "Net-(LINE_IN-PadT)") (class "Default")
      (node (ref "LINE_IN") (pin "T") (pinfunction "T_T") (pintype "bidirectional"))
      (node (ref "R8") (pin "2") (pinfunction "2_2") (pintype "passive"))
    )
    (net (code "40") (name "Net-(OUTPUT_SELECTB-NC)") (class "Default")
      (node (ref "LINE_OUT") (pin "R") (pinfunction "R_R") (pintype "bidirectional"))
      (node (ref "OUTPUT_SELECT") (pin "2") (pinfunction "NC_2") (pintype "passive"))
    )
    (net (code "41") (name "Net-(OUTPUT_SELECTB-NO)") (class "Default")
      (node (ref "OUTPUT_SELECT") (pin "4") (pinfunction "NO_4") (pintype "passive"))
      (node (ref "R9") (pin "1") (pinfunction "1_1") (pintype "passive"))
    )
    (net (code "42") (name "Net-(OUTPUT_SELECTC-NC)") (class "Default")
      (node (ref "LINE_OUT") (pin "T") (pinfunction "T_T") (pintype "bidirectional"))
      (node (ref "OUTPUT_SELECT") (pin "7") (pinfunction "NC_7") (pintype "passive"))
    )
    (net (code "43") (name "Net-(OUTPUT_SELECTC-NO)") (class "Default")
      (node (ref "OUTPUT_SELECT") (pin "5") (pinfunction "NO_5") (pintype "passive"))
      (node (ref "R10") (pin "1") (pinfunction "1_1") (pintype "passive"))
    )
    (net (code "44") (name "Net-(PCM5102-CAPM)") (class "Default")
      (node (ref "C33") (pin "1") (pinfunction "1_1") (pintype "passive"))
      (node (ref "PCM5102") (pin "4") (pinfunction "CAPM_4") (pintype "bidirectional"))
    )
    (net (code "45") (name "Net-(PCM5102-CAPP)") (class "Default")
      (node (ref "C33") (pin "2") (pinfunction "2_2") (pintype "passive"))
      (node (ref "PCM5102") (pin "2") (pinfunction "CAPP_2") (pintype "bidirectional"))
    )
    (net (code "46") (name "Net-(PCM5102-LDOO)") (class "Default")
      (node (ref "C10") (pin "1") (pinfunction "1_1") (pintype "passive"))
      (node (ref "C8") (pin "+") (pinfunction "+_+") (pintype "passive"))
      (node (ref "PCM5102") (pin "18") (pinfunction "LDOO_18") (pintype "bidirectional"))
    )
    (net (code "47") (name "Net-(PCM5102-OUTL)") (class "Default")
      (node (ref "PCM5102") (pin "6") (pinfunction "OUTL_6") (pintype "bidirectional"))
      (node (ref "R7") (pin "2") (pinfunction "2_2") (pintype "passive"))
    )
    (net (code "48") (name "Net-(PCM5102-OUTR)") (class "Default")
      (node (ref "PCM5102") (pin "7") (pinfunction "OUTR_7") (pintype "bidirectional"))
      (node (ref "R6") (pin "2") (pinfunction "2_2") (pintype "passive"))
    )
    (net (code "49") (name "Net-(PCM5102-VNEG)") (class "Default")
      (node (ref "C34") (pin "1") (pinfunction "1_1") (pintype "passive"))
      (node (ref "PCM5102") (pin "5") (pinfunction "VNEG_5") (pintype "bidirectional"))
    )
    (net (code "50") (name "Net-(POWERA-P)") (class "Default")
      (node (ref "AC_IN") (pin "PWR") (pinfunction "PWR_PWR") (pintype "bidirectional"))
      (node (ref "POWER") (pin "1") (pinfunction "P_1") (pintype "passive"))
      (node (ref "POWER") (pin "3") (pinfunction "P_3") (pintype "passive"))
    )
    (net (code "51") (name "Net-(POWERA-S)") (class "Default")
      (node (ref "D4") (pin "A") (pinfunction "A_A") (pintype "passive"))
      (node (ref "D6") (pin "C") (pinfunction "C_C") (pintype "passive"))
      (node (ref "POWER") (pin "2") (pinfunction "S_2") (pintype "passive"))
      (node (ref "POWER") (pin "4") (pinfunction "S_4") (pintype "passive"))
    )
    (net (code "52") (name "Net-(R24-Pad2)") (class "Default")
      (node (ref "R24") (pin "2") (pinfunction "2_2") (pintype "passive"))
      (node (ref "T1") (pin "B") (pinfunction "B_B") (pintype "passive"))
    )
    (net (code "53") (name "RST") (class "Default")
      (node (ref "CP2615") (pin "9") (pinfunction "~{RST}_9") (pintype "bidirectional"))
      (node (ref "PROG") (pin "1") (pinfunction "1_1") (pintype "bidirectional"))
      (node (ref "R4") (pin "1") (pinfunction "1_1") (pintype "passive"))
    )
    (net (code "54") (name "R_LL") (class "Default")
      (node (ref "C31") (pin "2") (pinfunction "2_2") (pintype "passive"))
      (node (ref "OUTPUT_SELECT") (pin "3") (pinfunction "W_3") (pintype "passive"))
      (node (ref "R6") (pin "1") (pinfunction "1_1") (pintype "passive"))
    )
    (net (code "55") (name "V+") (class "Default")
      (node (ref "555") (pin "4") (pinfunction "R_4") (pintype "input"))
      (node (ref "555") (pin "8") (pinfunction "V+_8") (pintype "power_in"))
      (node (ref "78XX") (pin "3") (pinfunction "VO_3") (pintype "passive"))
      (node (ref "AMP_L") (pin "8") (pinfunction "+V_8") (pintype "power_in"))
      (node (ref "AMP_R") (pin "8") (pinfunction "+V_8") (pintype "power_in"))
      (node (ref "BUFFER_L") (pin "5") (pinfunction "VCC_5") (pintype "input"))
      (node (ref "BUFFER_R") (pin "5") (pinfunction "VCC_5") (pintype "input"))
      (node (ref "C16") (pin "2") (pinfunction "2_2") (pintype "passive"))
      (node (ref "C17") (pin "2") (pinfunction "2_2") (pintype "passive"))
      (node (ref "C19") (pin "+") (pinfunction "+_+") (pintype "passive"))
      (node (ref "C24") (pin "2") (pinfunction "2_2") (pintype "passive"))
      (node (ref "C25") (pin "2") (pinfunction "2_2") (pintype "passive"))
      (node (ref "C27") (pin "+") (pinfunction "+_+") (pintype "passive"))
      (node (ref "C43") (pin "+") (pinfunction "+_+") (pintype "passive"))
      (node (ref "C5") (pin "1") (pinfunction "1_1") (pintype "passive"))
      (node (ref "C6") (pin "1") (pinfunction "1_1") (pintype "passive"))
      (node (ref "C7") (pin "1") (pinfunction "1_1") (pintype "passive"))
      (node (ref "D10") (pin "C") (pinfunction "C_C") (pintype "passive"))
      (node (ref "D2") (pin "C") (pinfunction "C_C") (pintype "passive"))
      (node (ref "D8") (pin "A") (pinfunction "A_A") (pintype "passive"))
      (node (ref "OUTPUT_SELECT") (pin "8") (pinfunction "+_8") (pintype "passive"))
      (node (ref "R12") (pin "2") (pinfunction "2_2") (pintype "passive"))
      (node (ref "T1") (pin "C") (pinfunction "C_C") (pintype "passive"))
    )
    (net (code "56") (name "V-") (class "Default")
      (node (ref "79XX") (pin "3") (pinfunction "VO_3") (pintype "passive"))
      (node (ref "AMP_L") (pin "4") (pinfunction "GND_4") (pintype "power_in"))
      (node (ref "AMP_R") (pin "4") (pinfunction "GND_4") (pintype "power_in"))
      (node (ref "BUFFER_L") (pin "1") (pinfunction "BW_1") (pintype "passive"))
      (node (ref "BUFFER_L") (pin "3") (pinfunction "VEE_3") (pintype "input"))
      (node (ref "BUFFER_L") (pin "6") (pinfunction "VEE_6") (pintype "input"))
      (node (ref "BUFFER_R") (pin "1") (pinfunction "BW_1") (pintype "passive"))
      (node (ref "BUFFER_R") (pin "3") (pinfunction "VEE_3") (pintype "input"))
      (node (ref "BUFFER_R") (pin "6") (pinfunction "VEE_6") (pintype "input"))
      (node (ref "C12") (pin "2") (pinfunction "2_2") (pintype "passive"))
      (node (ref "C15") (pin "2") (pinfunction "2_2") (pintype "passive"))
      (node (ref "C18") (pin "2") (pinfunction "2_2") (pintype "passive"))
      (node (ref "C20") (pin "-") (pinfunction "-_-") (pintype "passive"))
      (node (ref "C23") (pin "2") (pinfunction "2_2") (pintype "passive"))
      (node (ref "C26") (pin "2") (pinfunction "2_2") (pintype "passive"))
      (node (ref "C28") (pin "-") (pinfunction "-_-") (pintype "passive"))
      (node (ref "C42") (pin "-") (pinfunction "-_-") (pintype "passive"))
      (node (ref "D7") (pin "C") (pinfunction "C_C") (pintype "passive"))
      (node (ref "D9") (pin "A") (pinfunction "A_A") (pintype "passive"))
      (node (ref "R12") (pin "1") (pinfunction "1_1") (pintype "passive"))
    )
    (net (code "57") (name "unconnected-(555-CV-Pad5)") (class "Default")
      (node (ref "555") (pin "5") (pinfunction "CV_5") (pintype "input"))
    )
    (net (code "58") (name "unconnected-(555-DIS-Pad7)") (class "Default")
      (node (ref "555") (pin "7") (pinfunction "DIS_7") (pintype "input"))
    )
    (net (code "59") (name "unconnected-(CP2615-GPIO1-Pad17)") (class "Default")
      (node (ref "CP2615") (pin "17") (pinfunction "GPIO1_17") (pintype "bidirectional"))
    )
    (net (code "60") (name "unconnected-(CP2615-GPIO2-Pad16)") (class "Default")
      (node (ref "CP2615") (pin "16") (pinfunction "GPIO2_16") (pintype "bidirectional"))
    )
    (net (code "61") (name "unconnected-(CP2615-GPIO3-Pad15)") (class "Default")
      (node (ref "CP2615") (pin "15") (pinfunction "GPIO3_15") (pintype "bidirectional"))
    )
    (net (code "62") (name "unconnected-(CP2615-GPIO4-Pad14)") (class "Default")
      (node (ref "CP2615") (pin "14") (pinfunction "GPIO4_14") (pintype "bidirectional"))
    )
    (net (code "63") (name "unconnected-(CP2615-GPIO5-Pad13)") (class "Default")
      (node (ref "CP2615") (pin "13") (pinfunction "GPIO5_13") (pintype "bidirectional"))
    )
    (net (code "64") (name "unconnected-(CP2615-GPIO6-Pad12)") (class "Default")
      (node (ref "CP2615") (pin "12") (pinfunction "GPIO6_12") (pintype "bidirectional"))
    )
    (net (code "65") (name "unconnected-(CP2615-GPIO7-Pad11)") (class "Default")
      (node (ref "CP2615") (pin "11") (pinfunction "GPIO7_11") (pintype "bidirectional"))
    )
    (net (code "66") (name "unconnected-(CP2615-GPIO8{slash}ADC-Pad20)") (class "Default")
      (node (ref "CP2615") (pin "20") (pinfunction "GPIO8/ADC_20") (pintype "bidirectional"))
    )
    (net (code "67") (name "unconnected-(CP2615-GPIO9{slash}BUTTONS-Pad19)") (class "Default")
      (node (ref "CP2615") (pin "19") (pinfunction "GPIO9/BUTTONS_19") (pintype "bidirectional"))
    )
    (net (code "68") (name "unconnected-(CP2615-GPIO10{slash}RESETOUT-Pad22)") (class "Default")
      (node (ref "CP2615") (pin "22") (pinfunction "GPIO10/RESETOUT_22") (pintype "bidirectional"))
    )
    (net (code "69") (name "unconnected-(CP2615-GPIO11{slash}RST-Pad27)") (class "Default")
      (node (ref "CP2615") (pin "27") (pinfunction "GPIO11/RST_27") (pintype "bidirectional"))
    )
    (net (code "70") (name "unconnected-(CP2615-GPIO12{slash}CLKOUT-Pad25)") (class "Default")
      (node (ref "CP2615") (pin "25") (pinfunction "GPIO12/CLKOUT_25") (pintype "bidirectional"))
    )
    (net (code "71") (name "unconnected-(CP2615-GPIO13{slash}TX-Pad24)") (class "Default")
      (node (ref "CP2615") (pin "24") (pinfunction "GPIO13/TX_24") (pintype "bidirectional"))
    )
    (net (code "72") (name "unconnected-(CP2615-GPIO14{slash}RX-Pad23)") (class "Default")
      (node (ref "CP2615") (pin "23") (pinfunction "GPIO14/RX_23") (pintype "bidirectional"))
    )
    (net (code "73") (name "unconnected-(CP2615-GPIO15{slash}CTS-Pad31)") (class "Default")
      (node (ref "CP2615") (pin "31") (pinfunction "GPIO15/CTS_31") (pintype "bidirectional"))
    )
    (net (code "74") (name "unconnected-(CP2615-SDIN-Pad1)") (class "Default")
      (node (ref "CP2615") (pin "1") (pinfunction "SDIN_1") (pintype "bidirectional"))
    )
    (net (code "75") (name "unconnected-(HEADPHONE_DELAYB-NC-Pad2)") (class "Default")
      (node (ref "HEADPHONE_DELAY") (pin "2") (pinfunction "NC_2") (pintype "passive"))
    )
    (net (code "76") (name "unconnected-(HEADPHONE_DELAYC-NC-Pad7)") (class "Default")
      (node (ref "HEADPHONE_DELAY") (pin "7") (pinfunction "NC_7") (pintype "passive"))
    )
    (net (code "77") (name "unconnected-(PROG-Pad3)") (class "Default")
      (node (ref "PROG") (pin "3") (pinfunction "3_3") (pintype "bidirectional"))
    )
    (net (code "78") (name "unconnected-(PROG-Pad5)") (class "Default")
      (node (ref "PROG") (pin "5") (pinfunction "5_5") (pintype "bidirectional"))
    )
    (net (code "79") (name "unconnected-(U$2-CC1-PadA5)") (class "Default")
      (node (ref "U$2") (pin "A5") (pinfunction "CC1_A5") (pintype "bidirectional"))
    )
    (net (code "80") (name "unconnected-(U$2-CC2-PadB5)") (class "Default")
      (node (ref "U$2") (pin "B5") (pinfunction "CC2_B5") (pintype "bidirectional"))
    )
    (net (code "81") (name "unconnected-(U$2-SBU1-PadA8)") (class "Default")
      (node (ref "U$2") (pin "A8") (pinfunction "SBU1_A8") (pintype "bidirectional"))
    )
    (net (code "82") (name "unconnected-(U$2-SBU2-PadB8)") (class "Default")
      (node (ref "U$2") (pin "B8") (pinfunction "SBU2_B8") (pintype "bidirectional"))
    )
    (net (code "83") (name "unconnected-(U$2-SSRXN1-PadA10)") (class "Default")
      (node (ref "U$2") (pin "A10") (pinfunction "SSRXN1_A10") (pintype "bidirectional"))
    )
    (net (code "84") (name "unconnected-(U$2-SSRXN2-PadB10)") (class "Default")
      (node (ref "U$2") (pin "B10") (pinfunction "SSRXN2_B10") (pintype "bidirectional"))
    )
    (net (code "85") (name "unconnected-(U$2-SSRXP1-PadA11)") (class "Default")
      (node (ref "U$2") (pin "A11") (pinfunction "SSRXP1_A11") (pintype "bidirectional"))
    )
    (net (code "86") (name "unconnected-(U$2-SSRXP2-PadB11)") (class "Default")
      (node (ref "U$2") (pin "B11") (pinfunction "SSRXP2_B11") (pintype "bidirectional"))
    )
    (net (code "87") (name "unconnected-(U$2-SSTXN1-PadA3)") (class "Default")
      (node (ref "U$2") (pin "A3") (pinfunction "SSTXN1_A3") (pintype "bidirectional"))
    )
    (net (code "88") (name "unconnected-(U$2-SSTXN2-PadB3)") (class "Default")
      (node (ref "U$2") (pin "B3") (pinfunction "SSTXN2_B3") (pintype "bidirectional"))
    )
    (net (code "89") (name "unconnected-(U$2-SSTXP1-PadA2)") (class "Default")
      (node (ref "U$2") (pin "A2") (pinfunction "SSTXP1_A2") (pintype "bidirectional"))
    )
    (net (code "90") (name "unconnected-(U$2-SSTXP2-PadB2)") (class "Default")
      (node (ref "U$2") (pin "B2") (pinfunction "SSTXP2_B2") (pintype "bidirectional"))
    )
  )
)
